# P09_CONNECT_LED.net
KiCad netlist of a schematic drawn in Altium Designer
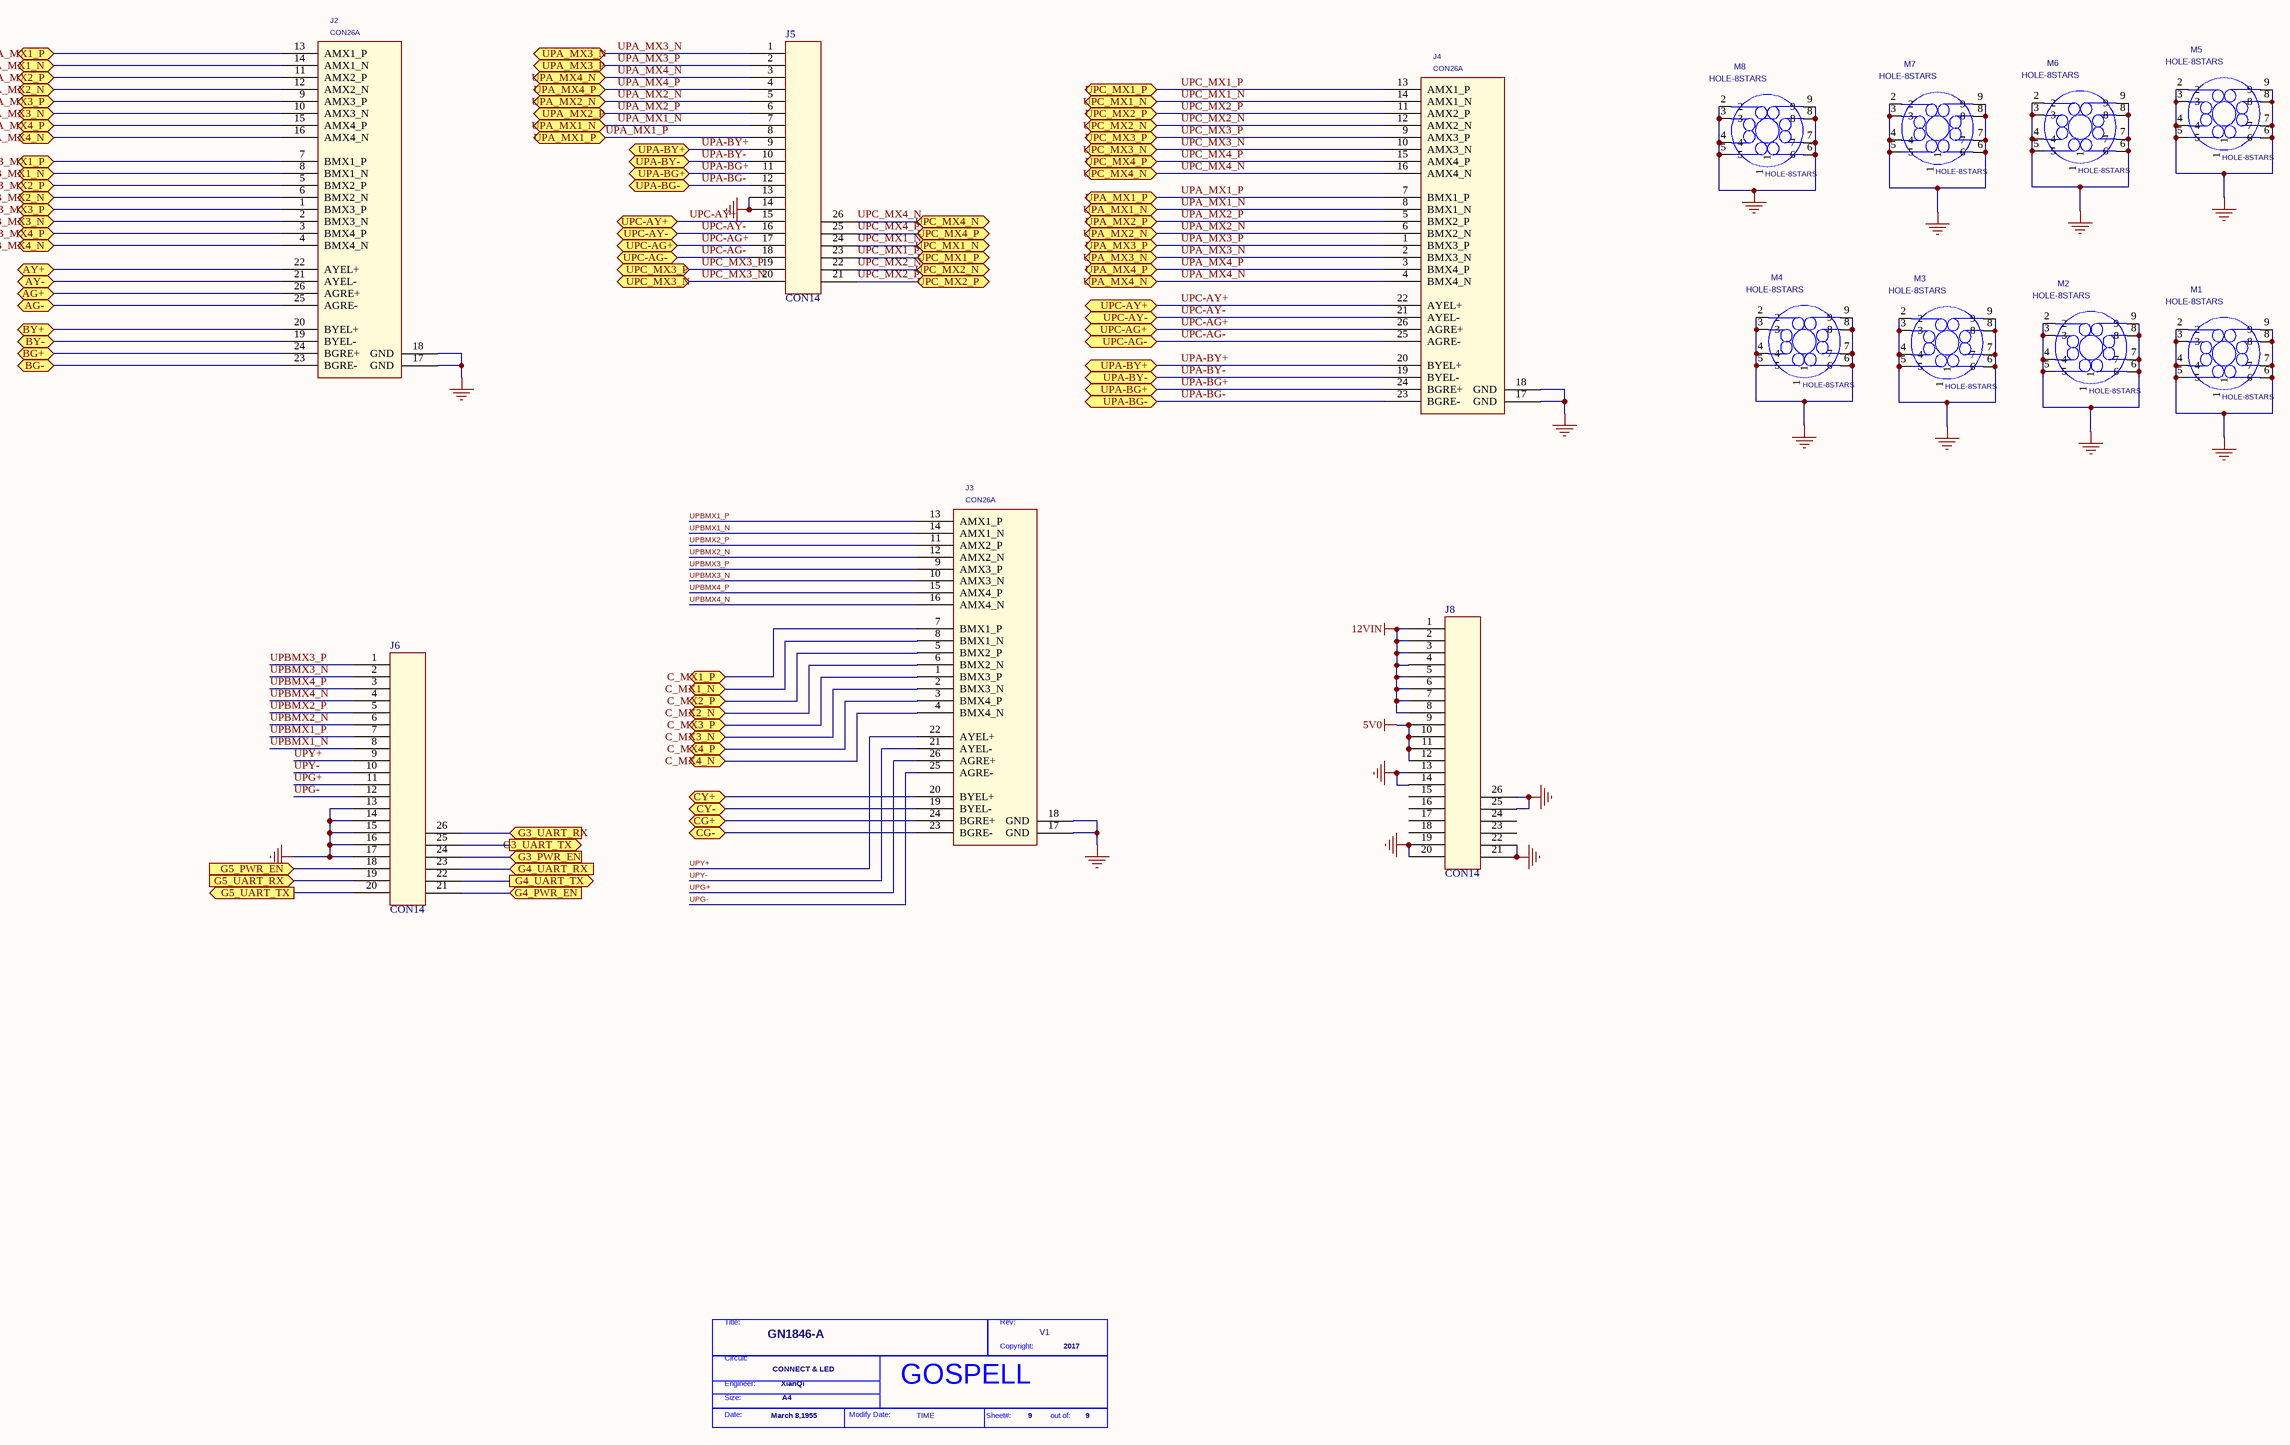
[diagram p0: P09 CONNECT & LED.SchDoc]

(export (version "E")
  (design (tool "Eeschema 10.0.6"))
  (components
    (comp (ref "J2") (value "CON26A") (libsource (lib "*") (part "CON26A_0")))
    (comp (ref "J3") (value "CON26A") (libsource (lib "*") (part "CON26A_0")))
    (comp (ref "J4") (value "CON26A") (libsource (lib "*") (part "CON26A_0")))
    (comp (ref "J5")
      (value "CON14")
      (footprint "HERDER13X2-2.0")
      (libsource (lib "GN-1846-B-V1_Library") (part "CON14"))
    )
    (comp (ref "J6")
      (value "CON14")
      (footprint "HERDER13X2-2.0")
      (libsource (lib "GN-1846-B-V1_Library") (part "CON14"))
    )
    (comp (ref "J8")
      (value "CON14")
      (footprint "HERDER13X2-2.0")
      (libsource (lib "GN-1846-B-V1_Library") (part "CON14"))
    )
    (comp (ref "M1")
      (value "HOLE-8STARS")
      (footprint "HK")
      (fields (field (name "DEVICE") "HOLE-8STARS"))
      (libsource (lib "*") (part "GEN35"))
    )
    (comp (ref "M2")
      (value "HOLE-8STARS")
      (footprint "HK")
      (fields (field (name "DEVICE") "HOLE-8STARS"))
      (libsource (lib "*") (part "GEN35"))
    )
    (comp (ref "M3")
      (value "HOLE-8STARS")
      (footprint "HK")
      (fields (field (name "DEVICE") "HOLE-8STARS"))
      (libsource (lib "*") (part "GEN35"))
    )
    (comp (ref "M4")
      (value "HOLE-8STARS")
      (footprint "HK")
      (fields (field (name "DEVICE") "HOLE-8STARS"))
      (libsource (lib "*") (part "GEN35"))
    )
    (comp (ref "M5")
      (value "HOLE-8STARS")
      (footprint "HK")
      (fields (field (name "DEVICE") "HOLE-8STARS"))
      (libsource (lib "*") (part "GEN35"))
    )
    (comp (ref "M6")
      (value "HOLE-8STARS")
      (footprint "HK")
      (fields (field (name "DEVICE") "HOLE-8STARS"))
      (libsource (lib "*") (part "GEN35"))
    )
    (comp (ref "M7")
      (value "HOLE-8STARS")
      (footprint "HK")
      (fields (field (name "DEVICE") "HOLE-8STARS"))
      (libsource (lib "*") (part "GEN35"))
    )
    (comp (ref "M8")
      (value "HOLE-8STARS")
      (footprint "HK")
      (fields (field (name "DEVICE") "HOLE-8STARS"))
      (libsource (lib "*") (part "GEN35"))
    )
  )
  (nets
    (net (code "1") (name "/AG+") (class "Default")
      (node (ref "J2") (pin "26") (pinfunction "AGRE+_26") (pintype "passive"))
    )
    (net (code "2") (name "/AG-") (class "Default")
      (node (ref "J2") (pin "25") (pinfunction "AGRE-_25") (pintype "passive"))
    )
    (net (code "3") (name "/AY+") (class "Default")
      (node (ref "J2") (pin "22") (pinfunction "AYEL+_22") (pintype "passive"))
    )
    (net (code "4") (name "/AY-") (class "Default")
      (node (ref "J2") (pin "21") (pinfunction "AYEL-_21") (pintype "passive"))
    )
    (net (code "5") (name "/A_MX1_N") (class "Default")
      (node (ref "J2") (pin "14") (pinfunction "AMX1_N_14") (pintype "passive"))
    )
    (net (code "6") (name "/A_MX1_P") (class "Default")
      (node (ref "J2") (pin "13") (pinfunction "AMX1_P_13") (pintype "passive"))
    )
    (net (code "7") (name "/A_MX2_N") (class "Default")
      (node (ref "J2") (pin "12") (pinfunction "AMX2_N_12") (pintype "passive"))
    )
    (net (code "8") (name "/A_MX2_P") (class "Default")
      (node (ref "J2") (pin "11") (pinfunction "AMX2_P_11") (pintype "passive"))
    )
    (net (code "9") (name "/A_MX3_N") (class "Default")
      (node (ref "J2") (pin "10") (pinfunction "AMX3_N_10") (pintype "passive"))
    )
    (net (code "10") (name "/A_MX3_P") (class "Default")
      (node (ref "J2") (pin "9") (pinfunction "AMX3_P_9") (pintype "passive"))
    )
    (net (code "11") (name "/A_MX4_N") (class "Default")
      (node (ref "J2") (pin "16") (pinfunction "AMX4_N_16") (pintype "passive"))
    )
    (net (code "12") (name "/A_MX4_P") (class "Default")
      (node (ref "J2") (pin "15") (pinfunction "AMX4_P_15") (pintype "passive"))
    )
    (net (code "13") (name "/BG+") (class "Default")
      (node (ref "J2") (pin "24") (pinfunction "BGRE+_24") (pintype "passive"))
    )
    (net (code "14") (name "/BG-") (class "Default")
      (node (ref "J2") (pin "23") (pinfunction "BGRE-_23") (pintype "passive"))
    )
    (net (code "15") (name "/BY+") (class "Default")
      (node (ref "J2") (pin "20") (pinfunction "BYEL+_20") (pintype "passive"))
    )
    (net (code "16") (name "/BY-") (class "Default")
      (node (ref "J2") (pin "19") (pinfunction "BYEL-_19") (pintype "passive"))
    )
    (net (code "17") (name "/B_MX1_N") (class "Default")
      (node (ref "J2") (pin "8") (pinfunction "BMX1_N_8") (pintype "passive"))
    )
    (net (code "18") (name "/B_MX1_P") (class "Default")
      (node (ref "J2") (pin "7") (pinfunction "BMX1_P_7") (pintype "passive"))
    )
    (net (code "19") (name "/B_MX2_N") (class "Default")
      (node (ref "J2") (pin "6") (pinfunction "BMX2_N_6") (pintype "passive"))
    )
    (net (code "20") (name "/B_MX2_P") (class "Default")
      (node (ref "J2") (pin "5") (pinfunction "BMX2_P_5") (pintype "passive"))
    )
    (net (code "21") (name "/B_MX3_N") (class "Default")
      (node (ref "J2") (pin "2") (pinfunction "BMX3_N_2") (pintype "passive"))
    )
    (net (code "22") (name "/B_MX3_P") (class "Default")
      (node (ref "J2") (pin "1") (pinfunction "BMX3_P_1") (pintype "passive"))
    )
    (net (code "23") (name "/B_MX4_N") (class "Default")
      (node (ref "J2") (pin "4") (pinfunction "BMX4_N_4") (pintype "passive"))
    )
    (net (code "24") (name "/B_MX4_P") (class "Default")
      (node (ref "J2") (pin "3") (pinfunction "BMX4_P_3") (pintype "passive"))
    )
    (net (code "25") (name "/CG+") (class "Default")
      (node (ref "J3") (pin "24") (pinfunction "BGRE+_24") (pintype "passive"))
    )
    (net (code "26") (name "/CG-") (class "Default")
      (node (ref "J3") (pin "23") (pinfunction "BGRE-_23") (pintype "passive"))
    )
    (net (code "27") (name "/CY+") (class "Default")
      (node (ref "J3") (pin "20") (pinfunction "BYEL+_20") (pintype "passive"))
    )
    (net (code "28") (name "/CY-") (class "Default")
      (node (ref "J3") (pin "19") (pinfunction "BYEL-_19") (pintype "passive"))
    )
    (net (code "29") (name "/C_MX1_N") (class "Default")
      (node (ref "J3") (pin "8") (pinfunction "BMX1_N_8") (pintype "passive"))
    )
    (net (code "30") (name "/C_MX1_P") (class "Default")
      (node (ref "J3") (pin "7") (pinfunction "BMX1_P_7") (pintype "passive"))
    )
    (net (code "31") (name "/C_MX2_N") (class "Default")
      (node (ref "J3") (pin "6") (pinfunction "BMX2_N_6") (pintype "passive"))
    )
    (net (code "32") (name "/C_MX2_P") (class "Default")
      (node (ref "J3") (pin "5") (pinfunction "BMX2_P_5") (pintype "passive"))
    )
    (net (code "33") (name "/C_MX3_N") (class "Default")
      (node (ref "J3") (pin "2") (pinfunction "BMX3_N_2") (pintype "passive"))
    )
    (net (code "34") (name "/C_MX3_P") (class "Default")
      (node (ref "J3") (pin "1") (pinfunction "BMX3_P_1") (pintype "passive"))
    )
    (net (code "35") (name "/C_MX4_N") (class "Default")
      (node (ref "J3") (pin "4") (pinfunction "BMX4_N_4") (pintype "passive"))
    )
    (net (code "36") (name "/C_MX4_P") (class "Default")
      (node (ref "J3") (pin "3") (pinfunction "BMX4_P_3") (pintype "passive"))
    )
    (net (code "37") (name "/G3_PWR_EN") (class "Default")
      (node (ref "J6") (pin "24") (pinfunction "14_24") (pintype "passive"))
    )
    (net (code "38") (name "/G3_UART_RX") (class "Default")
      (node (ref "J6") (pin "26") (pinfunction "14_26") (pintype "passive"))
    )
    (net (code "39") (name "/G3_UART_TX") (class "Default")
      (node (ref "J6") (pin "25") (pinfunction "14_25") (pintype "passive"))
    )
    (net (code "40") (name "/G4_PWR_EN") (class "Default")
      (node (ref "J6") (pin "21") (pinfunction "14_21") (pintype "passive"))
    )
    (net (code "41") (name "/G4_UART_RX") (class "Default")
      (node (ref "J6") (pin "23") (pinfunction "14_23") (pintype "passive"))
    )
    (net (code "42") (name "/G4_UART_TX") (class "Default")
      (node (ref "J6") (pin "22") (pinfunction "14_22") (pintype "passive"))
    )
    (net (code "43") (name "/G5_PWR_EN") (class "Default")
      (node (ref "J6") (pin "18") (pinfunction "14_18") (pintype "passive"))
    )
    (net (code "44") (name "/G5_UART_RX") (class "Default")
      (node (ref "J6") (pin "19") (pinfunction "14_19") (pintype "passive"))
    )
    (net (code "45") (name "/G5_UART_TX") (class "Default")
      (node (ref "J6") (pin "20") (pinfunction "14_20") (pintype "passive"))
    )
    (net (code "46") (name "/UPA-BG+") (class "Default")
      (node (ref "J4") (pin "24") (pinfunction "BGRE+_24") (pintype "passive"))
      (node (ref "J5") (pin "11") (pinfunction "11_11") (pintype "passive"))
    )
    (net (code "47") (name "/UPA-BG-") (class "Default")
      (node (ref "J4") (pin "23") (pinfunction "BGRE-_23") (pintype "passive"))
      (node (ref "J5") (pin "12") (pinfunction "12_12") (pintype "passive"))
    )
    (net (code "48") (name "/UPA-BY+") (class "Default")
      (node (ref "J4") (pin "20") (pinfunction "BYEL+_20") (pintype "passive"))
      (node (ref "J5") (pin "9") (pinfunction "9_9") (pintype "passive"))
    )
    (net (code "49") (name "/UPA-BY-") (class "Default")
      (node (ref "J4") (pin "19") (pinfunction "BYEL-_19") (pintype "passive"))
      (node (ref "J5") (pin "10") (pinfunction "10_10") (pintype "passive"))
    )
    (net (code "50") (name "/UPA_MX1_N") (class "Default")
      (node (ref "J4") (pin "8") (pinfunction "BMX1_N_8") (pintype "passive"))
      (node (ref "J5") (pin "7") (pinfunction "7_7") (pintype "passive"))
    )
    (net (code "51") (name "/UPA_MX1_P") (class "Default")
      (node (ref "J4") (pin "7") (pinfunction "BMX1_P_7") (pintype "passive"))
      (node (ref "J5") (pin "8") (pinfunction "8_8") (pintype "passive"))
    )
    (net (code "52") (name "/UPA_MX2_N") (class "Default")
      (node (ref "J4") (pin "6") (pinfunction "BMX2_N_6") (pintype "passive"))
      (node (ref "J5") (pin "5") (pinfunction "5_5") (pintype "passive"))
    )
    (net (code "53") (name "/UPA_MX2_P") (class "Default")
      (node (ref "J4") (pin "5") (pinfunction "BMX2_P_5") (pintype "passive"))
      (node (ref "J5") (pin "6") (pinfunction "6_6") (pintype "passive"))
    )
    (net (code "54") (name "/UPA_MX3_N") (class "Default")
      (node (ref "J4") (pin "2") (pinfunction "BMX3_N_2") (pintype "passive"))
      (node (ref "J5") (pin "1") (pinfunction "1_1") (pintype "passive"))
    )
    (net (code "55") (name "/UPA_MX3_P") (class "Default")
      (node (ref "J4") (pin "1") (pinfunction "BMX3_P_1") (pintype "passive"))
      (node (ref "J5") (pin "2") (pinfunction "2_2") (pintype "passive"))
    )
    (net (code "56") (name "/UPA_MX4_N") (class "Default")
      (node (ref "J4") (pin "4") (pinfunction "BMX4_N_4") (pintype "passive"))
      (node (ref "J5") (pin "3") (pinfunction "3_3") (pintype "passive"))
    )
    (net (code "57") (name "/UPA_MX4_P") (class "Default")
      (node (ref "J4") (pin "3") (pinfunction "BMX4_P_3") (pintype "passive"))
      (node (ref "J5") (pin "4") (pinfunction "4_4") (pintype "passive"))
    )
    (net (code "58") (name "/UPBMX1_N") (class "Default")
      (node (ref "J3") (pin "14") (pinfunction "AMX1_N_14") (pintype "passive"))
      (node (ref "J6") (pin "8") (pinfunction "8_8") (pintype "passive"))
    )
    (net (code "59") (name "/UPBMX1_P") (class "Default")
      (node (ref "J3") (pin "13") (pinfunction "AMX1_P_13") (pintype "passive"))
      (node (ref "J6") (pin "7") (pinfunction "7_7") (pintype "passive"))
    )
    (net (code "60") (name "/UPBMX2_N") (class "Default")
      (node (ref "J3") (pin "12") (pinfunction "AMX2_N_12") (pintype "passive"))
      (node (ref "J6") (pin "6") (pinfunction "6_6") (pintype "passive"))
    )
    (net (code "61") (name "/UPBMX2_P") (class "Default")
      (node (ref "J3") (pin "11") (pinfunction "AMX2_P_11") (pintype "passive"))
      (node (ref "J6") (pin "5") (pinfunction "5_5") (pintype "passive"))
    )
    (net (code "62") (name "/UPBMX3_N") (class "Default")
      (node (ref "J3") (pin "10") (pinfunction "AMX3_N_10") (pintype "passive"))
      (node (ref "J6") (pin "2") (pinfunction "2_2") (pintype "passive"))
    )
    (net (code "63") (name "/UPBMX3_P") (class "Default")
      (node (ref "J3") (pin "9") (pinfunction "AMX3_P_9") (pintype "passive"))
      (node (ref "J6") (pin "1") (pinfunction "1_1") (pintype "passive"))
    )
    (net (code "64") (name "/UPBMX4_N") (class "Default")
      (node (ref "J3") (pin "16") (pinfunction "AMX4_N_16") (pintype "passive"))
      (node (ref "J6") (pin "4") (pinfunction "4_4") (pintype "passive"))
    )
    (net (code "65") (name "/UPBMX4_P") (class "Default")
      (node (ref "J3") (pin "15") (pinfunction "AMX4_P_15") (pintype "passive"))
      (node (ref "J6") (pin "3") (pinfunction "3_3") (pintype "passive"))
    )
    (net (code "66") (name "/UPC-AG+") (class "Default")
      (node (ref "J4") (pin "26") (pinfunction "AGRE+_26") (pintype "passive"))
      (node (ref "J5") (pin "17") (pinfunction "14_17") (pintype "passive"))
    )
    (net (code "67") (name "/UPC-AG-") (class "Default")
      (node (ref "J4") (pin "25") (pinfunction "AGRE-_25") (pintype "passive"))
      (node (ref "J5") (pin "18") (pinfunction "14_18") (pintype "passive"))
    )
    (net (code "68") (name "/UPC-AY+") (class "Default")
      (node (ref "J4") (pin "22") (pinfunction "AYEL+_22") (pintype "passive"))
      (node (ref "J5") (pin "15") (pinfunction "14_15") (pintype "passive"))
    )
    (net (code "69") (name "/UPC-AY-") (class "Default")
      (node (ref "J4") (pin "21") (pinfunction "AYEL-_21") (pintype "passive"))
      (node (ref "J5") (pin "16") (pinfunction "14_16") (pintype "passive"))
    )
    (net (code "70") (name "/UPC_MX1_N") (class "Default")
      (node (ref "J4") (pin "14") (pinfunction "AMX1_N_14") (pintype "passive"))
      (node (ref "J5") (pin "24") (pinfunction "14_24") (pintype "passive"))
    )
    (net (code "71") (name "/UPC_MX1_P") (class "Default")
      (node (ref "J4") (pin "13") (pinfunction "AMX1_P_13") (pintype "passive"))
      (node (ref "J5") (pin "23") (pinfunction "14_23") (pintype "passive"))
    )
    (net (code "72") (name "/UPC_MX2_N") (class "Default")
      (node (ref "J4") (pin "12") (pinfunction "AMX2_N_12") (pintype "passive"))
      (node (ref "J5") (pin "22") (pinfunction "14_22") (pintype "passive"))
    )
    (net (code "73") (name "/UPC_MX2_P") (class "Default")
      (node (ref "J4") (pin "11") (pinfunction "AMX2_P_11") (pintype "passive"))
      (node (ref "J5") (pin "21") (pinfunction "14_21") (pintype "passive"))
    )
    (net (code "74") (name "/UPC_MX3_N") (class "Default")
      (node (ref "J4") (pin "10") (pinfunction "AMX3_N_10") (pintype "passive"))
      (node (ref "J5") (pin "20") (pinfunction "14_20") (pintype "passive"))
    )
    (net (code "75") (name "/UPC_MX3_P") (class "Default")
      (node (ref "J4") (pin "9") (pinfunction "AMX3_P_9") (pintype "passive"))
      (node (ref "J5") (pin "19") (pinfunction "14_19") (pintype "passive"))
    )
    (net (code "76") (name "/UPC_MX4_N") (class "Default")
      (node (ref "J4") (pin "16") (pinfunction "AMX4_N_16") (pintype "passive"))
      (node (ref "J5") (pin "26") (pinfunction "14_26") (pintype "passive"))
    )
    (net (code "77") (name "/UPC_MX4_P") (class "Default")
      (node (ref "J4") (pin "15") (pinfunction "AMX4_P_15") (pintype "passive"))
      (node (ref "J5") (pin "25") (pinfunction "14_25") (pintype "passive"))
    )
    (net (code "78") (name "/UPG+") (class "Default")
      (node (ref "J3") (pin "26") (pinfunction "AGRE+_26") (pintype "passive"))
      (node (ref "J6") (pin "11") (pinfunction "11_11") (pintype "passive"))
    )
    (net (code "79") (name "/UPG-") (class "Default")
      (node (ref "J3") (pin "25") (pinfunction "AGRE-_25") (pintype "passive"))
      (node (ref "J6") (pin "12") (pinfunction "12_12") (pintype "passive"))
    )
    (net (code "80") (name "/UPY+") (class "Default")
      (node (ref "J3") (pin "22") (pinfunction "AYEL+_22") (pintype "passive"))
      (node (ref "J6") (pin "9") (pinfunction "9_9") (pintype "passive"))
    )
    (net (code "81") (name "/UPY-") (class "Default")
      (node (ref "J3") (pin "21") (pinfunction "AYEL-_21") (pintype "passive"))
      (node (ref "J6") (pin "10") (pinfunction "10_10") (pintype "passive"))
    )
    (net (code "82") (name "5V0") (class "Default")
      (node (ref "J8") (pin "10") (pinfunction "10_10") (pintype "passive"))
      (node (ref "J8") (pin "11") (pinfunction "11_11") (pintype "passive"))
      (node (ref "J8") (pin "12") (pinfunction "12_12") (pintype "passive"))
      (node (ref "J8") (pin "9") (pinfunction "9_9") (pintype "passive"))
    )
    (net (code "83") (name "12VIN") (class "Default")
      (node (ref "J8") (pin "1") (pinfunction "1_1") (pintype "passive"))
      (node (ref "J8") (pin "2") (pinfunction "2_2") (pintype "passive"))
      (node (ref "J8") (pin "3") (pinfunction "3_3") (pintype "passive"))
      (node (ref "J8") (pin "4") (pinfunction "4_4") (pintype "passive"))
      (node (ref "J8") (pin "5") (pinfunction "5_5") (pintype "passive"))
      (node (ref "J8") (pin "6") (pinfunction "6_6") (pintype "passive"))
      (node (ref "J8") (pin "7") (pinfunction "7_7") (pintype "passive"))
      (node (ref "J8") (pin "8") (pinfunction "8_8") (pintype "passive"))
    )
    (net (code "84") (name "GND") (class "Default")
      (node (ref "J2") (pin "17") (pinfunction "GND_17") (pintype "passive"))
      (node (ref "J2") (pin "18") (pinfunction "GND_18") (pintype "passive"))
      (node (ref "J3") (pin "17") (pinfunction "GND_17") (pintype "passive"))
      (node (ref "J3") (pin "18") (pinfunction "GND_18") (pintype "passive"))
      (node (ref "J4") (pin "17") (pinfunction "GND_17") (pintype "passive"))
      (node (ref "J4") (pin "18") (pinfunction "GND_18") (pintype "passive"))
      (node (ref "J5") (pin "13") (pinfunction "13_13") (pintype "passive"))
      (node (ref "J5") (pin "14") (pinfunction "14_14") (pintype "passive"))
      (node (ref "J6") (pin "13") (pinfunction "13_13") (pintype "passive"))
      (node (ref "J6") (pin "14") (pinfunction "14_14") (pintype "passive"))
      (node (ref "J6") (pin "15") (pinfunction "14_15") (pintype "passive"))
      (node (ref "J6") (pin "16") (pinfunction "14_16") (pintype "passive"))
      (node (ref "J6") (pin "17") (pinfunction "14_17") (pintype "passive"))
      (node (ref "J8") (pin "13") (pinfunction "13_13") (pintype "passive"))
      (node (ref "J8") (pin "14") (pinfunction "14_14") (pintype "passive"))
      (node (ref "J8") (pin "19") (pinfunction "14_19") (pintype "passive"))
      (node (ref "J8") (pin "20") (pinfunction "14_20") (pintype "passive"))
      (node (ref "J8") (pin "21") (pinfunction "14_21") (pintype "passive"))
      (node (ref "J8") (pin "22") (pinfunction "14_22") (pintype "passive"))
      (node (ref "J8") (pin "25") (pinfunction "14_25") (pintype "passive"))
      (node (ref "J8") (pin "26") (pinfunction "14_26") (pintype "passive"))
      (node (ref "M1") (pin "2") (pinfunction "2_2") (pintype "passive"))
      (node (ref "M1") (pin "3") (pinfunction "3_3") (pintype "passive"))
      (node (ref "M1") (pin "4") (pinfunction "4_4") (pintype "passive"))
      (node (ref "M1") (pin "5") (pinfunction "5_5") (pintype "passive"))
      (node (ref "M1") (pin "6") (pinfunction "6_6") (pintype "passive"))
      (node (ref "M1") (pin "7") (pinfunction "7_7") (pintype "passive"))
      (node (ref "M1") (pin "8") (pinfunction "8_8") (pintype "passive"))
      (node (ref "M1") (pin "9") (pinfunction "9_9") (pintype "passive"))
      (node (ref "M2") (pin "2") (pinfunction "2_2") (pintype "passive"))
      (node (ref "M2") (pin "3") (pinfunction "3_3") (pintype "passive"))
      (node (ref "M2") (pin "4") (pinfunction "4_4") (pintype "passive"))
      (node (ref "M2") (pin "5") (pinfunction "5_5") (pintype "passive"))
      (node (ref "M2") (pin "6") (pinfunction "6_6") (pintype "passive"))
      (node (ref "M2") (pin "7") (pinfunction "7_7") (pintype "passive"))
      (node (ref "M2") (pin "8") (pinfunction "8_8") (pintype "passive"))
      (node (ref "M2") (pin "9") (pinfunction "9_9") (pintype "passive"))
      (node (ref "M3") (pin "2") (pinfunction "2_2") (pintype "passive"))
      (node (ref "M3") (pin "3") (pinfunction "3_3") (pintype "passive"))
      (node (ref "M3") (pin "4") (pinfunction "4_4") (pintype "passive"))
      (node (ref "M3") (pin "5") (pinfunction "5_5") (pintype "passive"))
      (node (ref "M3") (pin "6") (pinfunction "6_6") (pintype "passive"))
      (node (ref "M3") (pin "7") (pinfunction "7_7") (pintype "passive"))
      (node (ref "M3") (pin "8") (pinfunction "8_8") (pintype "passive"))
      (node (ref "M3") (pin "9") (pinfunction "9_9") (pintype "passive"))
      (node (ref "M4") (pin "2") (pinfunction "2_2") (pintype "passive"))
      (node (ref "M4") (pin "3") (pinfunction "3_3") (pintype "passive"))
      (node (ref "M4") (pin "4") (pinfunction "4_4") (pintype "passive"))
      (node (ref "M4") (pin "5") (pinfunction "5_5") (pintype "passive"))
      (node (ref "M4") (pin "6") (pinfunction "6_6") (pintype "passive"))
      (node (ref "M4") (pin "7") (pinfunction "7_7") (pintype "passive"))
      (node (ref "M4") (pin "8") (pinfunction "8_8") (pintype "passive"))
      (node (ref "M4") (pin "9") (pinfunction "9_9") (pintype "passive"))
      (node (ref "M5") (pin "2") (pinfunction "2_2") (pintype "passive"))
      (node (ref "M5") (pin "3") (pinfunction "3_3") (pintype "passive"))
      (node (ref "M5") (pin "4") (pinfunction "4_4") (pintype "passive"))
      (node (ref "M5") (pin "5") (pinfunction "5_5") (pintype "passive"))
      (node (ref "M5") (pin "6") (pinfunction "6_6") (pintype "passive"))
      (node (ref "M5") (pin "7") (pinfunction "7_7") (pintype "passive"))
      (node (ref "M5") (pin "8") (pinfunction "8_8") (pintype "passive"))
      (node (ref "M5") (pin "9") (pinfunction "9_9") (pintype "passive"))
      (node (ref "M6") (pin "2") (pinfunction "2_2") (pintype "passive"))
      (node (ref "M6") (pin "3") (pinfunction "3_3") (pintype "passive"))
      (node (ref "M6") (pin "4") (pinfunction "4_4") (pintype "passive"))
      (node (ref "M6") (pin "5") (pinfunction "5_5") (pintype "passive"))
      (node (ref "M6") (pin "6") (pinfunction "6_6") (pintype "passive"))
      (node (ref "M6") (pin "7") (pinfunction "7_7") (pintype "passive"))
      (node (ref "M6") (pin "8") (pinfunction "8_8") (pintype "passive"))
      (node (ref "M6") (pin "9") (pinfunction "9_9") (pintype "passive"))
      (node (ref "M7") (pin "2") (pinfunction "2_2") (pintype "passive"))
      (node (ref "M7") (pin "3") (pinfunction "3_3") (pintype "passive"))
      (node (ref "M7") (pin "4") (pinfunction "4_4") (pintype "passive"))
      (node (ref "M7") (pin "5") (pinfunction "5_5") (pintype "passive"))
      (node (ref "M7") (pin "6") (pinfunction "6_6") (pintype "passive"))
      (node (ref "M7") (pin "7") (pinfunction "7_7") (pintype "passive"))
      (node (ref "M7") (pin "8") (pinfunction "8_8") (pintype "passive"))
      (node (ref "M7") (pin "9") (pinfunction "9_9") (pintype "passive"))
      (node (ref "M8") (pin "2") (pinfunction "2_2") (pintype "passive"))
      (node (ref "M8") (pin "3") (pinfunction "3_3") (pintype "passive"))
      (node (ref "M8") (pin "4") (pinfunction "4_4") (pintype "passive"))
      (node (ref "M8") (pin "5") (pinfunction "5_5") (pintype "passive"))
      (node (ref "M8") (pin "6") (pinfunction "6_6") (pintype "passive"))
      (node (ref "M8") (pin "7") (pinfunction "7_7") (pintype "passive"))
      (node (ref "M8") (pin "8") (pinfunction "8_8") (pintype "passive"))
      (node (ref "M8") (pin "9") (pinfunction "9_9") (pintype "passive"))
    )
    (net (code "85") (name "unconnected-(J8-14-Pad15)") (class "Default")
      (node (ref "J8") (pin "15") (pinfunction "14_15") (pintype "passive"))
    )
    (net (code "86") (name "unconnected-(J8-14-Pad16)") (class "Default")
      (node (ref "J8") (pin "16") (pinfunction "14_16") (pintype "passive"))
    )
    (net (code "87") (name "unconnected-(J8-14-Pad17)") (class "Default")
      (node (ref "J8") (pin "17") (pinfunction "14_17") (pintype "passive"))
    )
    (net (code "88") (name "unconnected-(J8-14-Pad18)") (class "Default")
      (node (ref "J8") (pin "18") (pinfunction "14_18") (pintype "passive"))
    )
    (net (code "89") (name "unconnected-(J8-14-Pad23)") (class "Default")
      (node (ref "J8") (pin "23") (pinfunction "14_23") (pintype "passive"))
    )
    (net (code "90") (name "unconnected-(J8-14-Pad24)") (class "Default")
      (node (ref "J8") (pin "24") (pinfunction "14_24") (pintype "passive"))
    )
    (net (code "91") (name "unconnected-(M1-Pad1)") (class "Default")
      (node (ref "M1") (pin "1") (pinfunction "1_1") (pintype "passive"))
    )
    (net (code "92") (name "unconnected-(M2-Pad1)") (class "Default")
      (node (ref "M2") (pin "1") (pinfunction "1_1") (pintype "passive"))
    )
    (net (code "93") (name "unconnected-(M3-Pad1)") (class "Default")
      (node (ref "M3") (pin "1") (pinfunction "1_1") (pintype "passive"))
    )
    (net (code "94") (name "unconnected-(M4-Pad1)") (class "Default")
      (node (ref "M4") (pin "1") (pinfunction "1_1") (pintype "passive"))
    )
    (net (code "95") (name "unconnected-(M5-Pad1)") (class "Default")
      (node (ref "M5") (pin "1") (pinfunction "1_1") (pintype "passive"))
    )
    (net (code "96") (name "unconnected-(M6-Pad1)") (class "Default")
      (node (ref "M6") (pin "1") (pinfunction "1_1") (pintype "passive"))
    )
    (net (code "97") (name "unconnected-(M7-Pad1)") (class "Default")
      (node (ref "M7") (pin "1") (pinfunction "1_1") (pintype "passive"))
    )
    (net (code "98") (name "unconnected-(M8-Pad1)") (class "Default")
      (node (ref "M8") (pin "1") (pinfunction "1_1") (pintype "passive"))
    )
  )
)
